# hamilton-3c.net
KiCad netlist of a schematic drawn in EAGLE
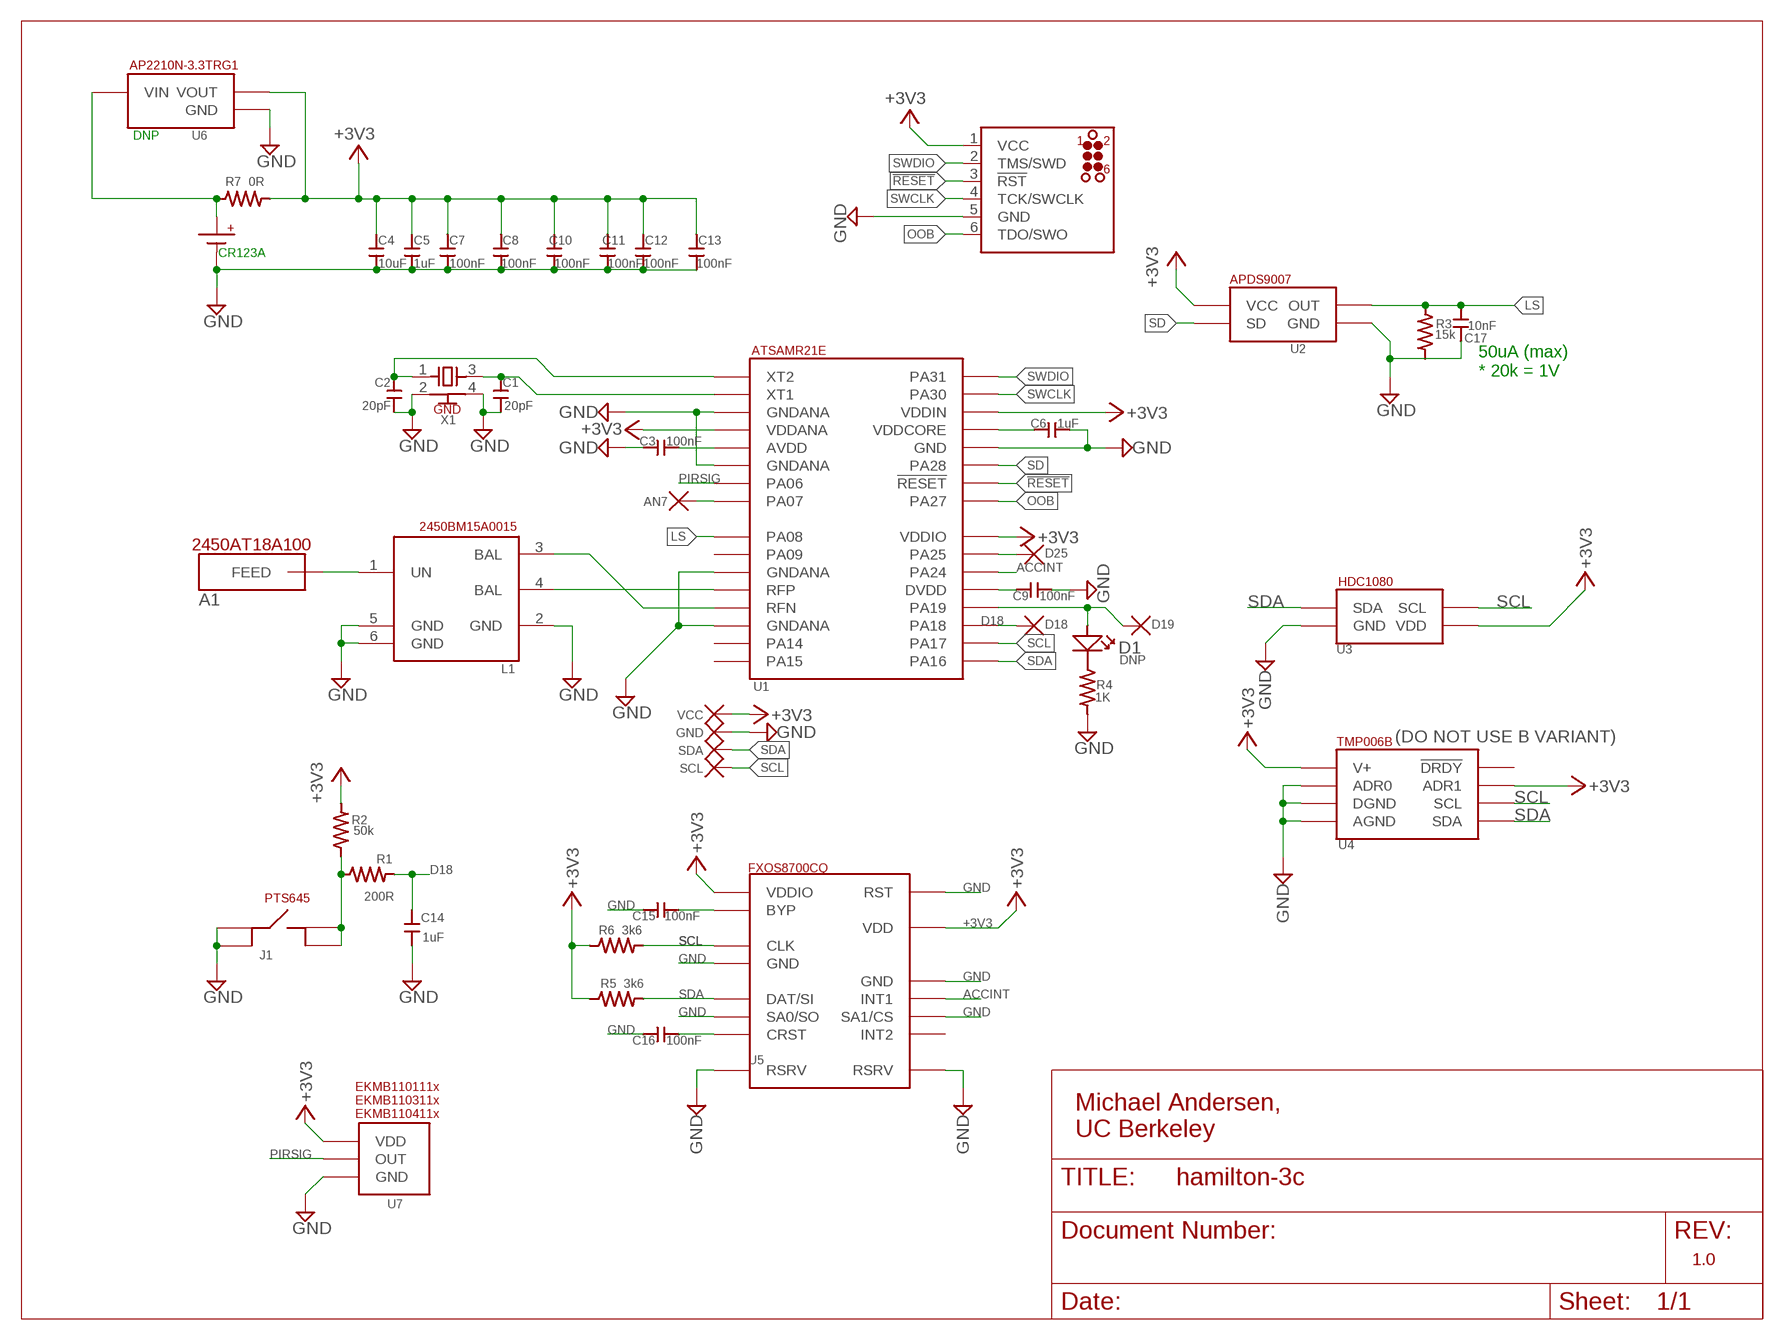
[diagram p0: schematic, sheet 1]

(export (version "E")
  (design (tool "Eeschema 10.0.6"))
  (components
    (comp (ref "A1")
      (value "JOHANSON_ANTENNA2")
      (footprint "eagle-import:JOHANSON_ANTENNA2")
      (libsource (lib "eagle-import") (part "JOHANSON_ANTENNA2"))
    )
    (comp (ref "BT1")
      (value "2/3A")
      (footprint "eagle-import:2_3A")
      (libsource (lib "eagle-import") (part "2/3A"))
    )
    (comp (ref "C1")
      (value "20pF")
      (footprint "eagle-import:S0402")
      (libsource (lib "eagle-import") (part "0603_CAPACITORSMALL"))
    )
    (comp (ref "C2")
      (value "20pF")
      (footprint "eagle-import:S0402")
      (libsource (lib "eagle-import") (part "0603_CAPACITORSMALL"))
    )
    (comp (ref "C3")
      (value "100nF")
      (footprint "eagle-import:S0402")
      (libsource (lib "eagle-import") (part "0603_CAPACITORSMALL"))
    )
    (comp (ref "C4")
      (value "10uF")
      (footprint "eagle-import:0805")
      (libsource (lib "eagle-import") (part "0805_CAPACITOR"))
    )
    (comp (ref "C5")
      (value "1uF")
      (footprint "eagle-import:S0402")
      (libsource (lib "eagle-import") (part "0603_CAPACITORSMALL"))
    )
    (comp (ref "C6")
      (value "1uF")
      (footprint "eagle-import:S0402")
      (libsource (lib "eagle-import") (part "0603_CAPACITORSMALL"))
    )
    (comp (ref "C7")
      (value "100nF")
      (footprint "eagle-import:S0402")
      (libsource (lib "eagle-import") (part "0603_CAPACITORSMALL"))
    )
    (comp (ref "C8")
      (value "100nF")
      (footprint "eagle-import:S0402")
      (libsource (lib "eagle-import") (part "0603_CAPACITORSMALL"))
    )
    (comp (ref "C9")
      (value "100nF")
      (footprint "eagle-import:S0402")
      (libsource (lib "eagle-import") (part "0603_CAPACITORSMALL"))
    )
    (comp (ref "C10")
      (value "100nF")
      (footprint "eagle-import:S0402")
      (libsource (lib "eagle-import") (part "0603_CAPACITORSMALL"))
    )
    (comp (ref "C11")
      (value "100nF")
      (footprint "eagle-import:S0402")
      (libsource (lib "eagle-import") (part "0603_CAPACITORSMALL"))
    )
    (comp (ref "C12")
      (value "100nF")
      (footprint "eagle-import:S0402")
      (libsource (lib "eagle-import") (part "0603_CAPACITORSMALL"))
    )
    (comp (ref "C13")
      (value "100nF")
      (footprint "eagle-import:S0402")
      (libsource (lib "eagle-import") (part "0603_CAPACITORSMALL"))
    )
    (comp (ref "C14")
      (value "1uF")
      (footprint "eagle-import:S0402")
      (libsource (lib "eagle-import") (part "0603_CAPACITORSMALL"))
    )
    (comp (ref "C15")
      (value "100nF")
      (footprint "eagle-import:S0402")
      (libsource (lib "eagle-import") (part "0603_CAPACITORSMALL"))
    )
    (comp (ref "C16")
      (value "100nF")
      (footprint "eagle-import:S0402")
      (libsource (lib "eagle-import") (part "0603_CAPACITORSMALL"))
    )
    (comp (ref "C17")
      (value "10nF")
      (footprint "eagle-import:S0402")
      (libsource (lib "eagle-import") (part "0603_CAPACITORSMALL"))
    )
    (comp (ref "D1")
      (value "DNP")
      (footprint "eagle-import:LINE_0603")
      (libsource (lib "eagle-import") (part "STATLEDLINE"))
    )
    (comp (ref "J1")
      (value "PTS645")
      (footprint "eagle-import:PTS645")
      (libsource (lib "eagle-import") (part "PTS645"))
    )
    (comp (ref "L1")
      (value "BALUN_JOHANSON")
      (footprint "eagle-import:BALUN_JOHANSON")
      (libsource (lib "eagle-import") (part "BALUN_JOHANSON"))
    )
    (comp (ref "R1")
      (value "200R")
      (footprint "eagle-import:S0402")
      (libsource (lib "eagle-import") (part "0603_RESISTORSMALL"))
    )
    (comp (ref "R2")
      (value "50k")
      (footprint "eagle-import:S0402")
      (libsource (lib "eagle-import") (part "0603_RESISTORSMALL"))
    )
    (comp (ref "R3")
      (value "15k")
      (footprint "eagle-import:S0402")
      (libsource (lib "eagle-import") (part "0603_RESISTORSMALL"))
    )
    (comp (ref "R4")
      (value "1K")
      (footprint "eagle-import:S0402")
      (libsource (lib "eagle-import") (part "0603_RESISTORSMALL"))
    )
    (comp (ref "R5")
      (value "3k6")
      (footprint "eagle-import:S0402")
      (libsource (lib "eagle-import") (part "0603_RESISTORSMALL"))
    )
    (comp (ref "R6")
      (value "3k6")
      (footprint "eagle-import:S0402")
      (libsource (lib "eagle-import") (part "0603_RESISTORSMALL"))
    )
    (comp (ref "R7")
      (value "0R")
      (footprint "eagle-import:S0402")
      (libsource (lib "eagle-import") (part "0603_RESISTORSMALL"))
    )
    (comp (ref "TP1")
      (value "D19")
      (footprint "eagle-import:TPP")
      (libsource (lib "eagle-import") (part "TP"))
    )
    (comp (ref "TP2")
      (value "D18")
      (footprint "eagle-import:TPP")
      (libsource (lib "eagle-import") (part "TP"))
    )
    (comp (ref "TP3")
      (value "AN7")
      (footprint "eagle-import:TPP")
      (libsource (lib "eagle-import") (part "TP"))
    )
    (comp (ref "TP4")
      (value "D25")
      (footprint "eagle-import:TPP")
      (libsource (lib "eagle-import") (part "TP"))
    )
    (comp (ref "TP5")
      (value "VCC")
      (footprint "eagle-import:TPP")
      (libsource (lib "eagle-import") (part "TP"))
    )
    (comp (ref "TP6")
      (value "GND")
      (footprint "eagle-import:TPP")
      (libsource (lib "eagle-import") (part "TP"))
    )
    (comp (ref "TP7")
      (value "SDA")
      (footprint "eagle-import:TPP")
      (libsource (lib "eagle-import") (part "TP"))
    )
    (comp (ref "TP8")
      (value "SCL")
      (footprint "eagle-import:TPP")
      (libsource (lib "eagle-import") (part "TP"))
    )
    (comp (ref "U$1")
      (value "JLINK_CONNECTWL")
      (footprint "eagle-import:TC2030-MCP")
      (libsource (lib "eagle-import") (part "JLINK_CONNECTWL"))
    )
    (comp (ref "U1")
      (value "SAMR21")
      (footprint "eagle-import:QFN32")
      (libsource (lib "eagle-import") (part "SAMR21"))
    )
    (comp (ref "U2")
      (value "APDS9007")
      (footprint "eagle-import:APDS9007")
      (libsource (lib "eagle-import") (part "APDS9007"))
    )
    (comp (ref "U3")
      (value "HDC1080")
      (footprint "eagle-import:WSON_HDC1080")
      (libsource (lib "eagle-import") (part "HDC1080"))
    )
    (comp (ref "U4")
      (value "TMP006B")
      (footprint "eagle-import:TMP006")
      (libsource (lib "eagle-import") (part "TMP006B"))
    )
    (comp (ref "U5")
      (value "ACCEL_FXOS8700CQ")
      (footprint "eagle-import:TQFN16")
      (libsource (lib "eagle-import") (part "ACCEL_FXOS8700CQ"))
    )
    (comp (ref "U6")
      (value "SOT23-3VREG")
      (footprint "eagle-import:SOT23")
      (libsource (lib "eagle-import") (part "SOT23-3VREG"))
    )
    (comp (ref "U7")
      (value "PANASONIC_PIR")
      (footprint "eagle-import:PIR")
      (libsource (lib "eagle-import") (part "PANASONIC_PIR"))
    )
    (comp (ref "X1")
      (value "XTAL")
      (footprint "eagle-import:XTAL")
      (libsource (lib "eagle-import") (part "XTAL"))
    )
  )
  (nets
    (net (code "1") (name "+3V3") (class "Default")
      (node (ref "C10") (pin "P$1") (pinfunction "P$1_P$1") (pintype "passive"))
      (node (ref "C11") (pin "P$1") (pinfunction "P$1_P$1") (pintype "passive"))
      (node (ref "C12") (pin "P$1") (pinfunction "P$1_P$1") (pintype "passive"))
      (node (ref "C13") (pin "P$1") (pinfunction "P$1_P$1") (pintype "passive"))
      (node (ref "C4") (pin "2") (pinfunction "P$2_2") (pintype "passive"))
      (node (ref "C5") (pin "P$2") (pinfunction "P$2_P$2") (pintype "passive"))
      (node (ref "C7") (pin "P$1") (pinfunction "P$1_P$1") (pintype "passive"))
      (node (ref "C8") (pin "P$1") (pinfunction "P$1_P$1") (pintype "passive"))
      (node (ref "R2") (pin "P$1") (pinfunction "P$1_P$1") (pintype "passive"))
      (node (ref "R5") (pin "P$2") (pinfunction "P$2_P$2") (pintype "passive"))
      (node (ref "R6") (pin "P$2") (pinfunction "P$2_P$2") (pintype "passive"))
      (node (ref "R7") (pin "P$1") (pinfunction "P$1_P$1") (pintype "passive"))
      (node (ref "TP5") (pin "P$1") (pinfunction "P$1_P$1") (pintype "bidirectional"))
      (node (ref "U$1") (pin "1") (pinfunction "VCC_1") (pintype "passive"))
      (node (ref "U1") (pin "24") (pinfunction "VDDIO_24") (pintype "bidirectional"))
      (node (ref "U1") (pin "30") (pinfunction "VDDIN_30") (pintype "bidirectional"))
      (node (ref "U1") (pin "4") (pinfunction "VDDANA_4") (pintype "bidirectional"))
      (node (ref "U2") (pin "4") (pinfunction "VCC_4") (pintype "bidirectional"))
      (node (ref "U3") (pin "5") (pinfunction "VDD_5") (pintype "bidirectional"))
      (node (ref "U4") (pin "A3") (pinfunction "V+_A3") (pintype "bidirectional"))
      (node (ref "U4") (pin "B1") (pinfunction "ADR1_B1") (pintype "bidirectional"))
      (node (ref "U5") (pin "P1") (pinfunction "VDDIO_P1") (pintype "bidirectional"))
      (node (ref "U5") (pin "P14") (pinfunction "VDD_P14") (pintype "bidirectional"))
      (node (ref "U6") (pin "2") (pinfunction "VOUT_2") (pintype "bidirectional"))
      (node (ref "U7") (pin "VDD") (pinfunction "VDD_VDD") (pintype "bidirectional"))
    )
    (net (code "2") (name "/ACCINT") (class "Default")
      (node (ref "U1") (pin "22") (pinfunction "PA24_22") (pintype "bidirectional"))
      (node (ref "U5") (pin "P11") (pinfunction "INT1_P11") (pintype "bidirectional"))
    )
    (net (code "3") (name "/D18") (class "Default")
      (node (ref "C14") (pin "P$2") (pinfunction "P$2_P$2") (pintype "passive"))
      (node (ref "R1") (pin "P$1") (pinfunction "P$1_P$1") (pintype "passive"))
      (node (ref "TP2") (pin "P$1") (pinfunction "P$1_P$1") (pintype "bidirectional"))
      (node (ref "U1") (pin "19") (pinfunction "PA18_19") (pintype "bidirectional"))
    )
    (net (code "4") (name "/PIRSIG") (class "Default")
      (node (ref "U1") (pin "7") (pinfunction "PA06_7") (pintype "bidirectional"))
      (node (ref "U7") (pin "OUT") (pinfunction "OUT_OUT") (pintype "bidirectional"))
    )
    (net (code "5") (name "/~{RESET}") (class "Default")
      (node (ref "U$1") (pin "3") (pinfunction "~{RST}_3") (pintype "bidirectional"))
      (node (ref "U1") (pin "26") (pinfunction "~{RESET}_26") (pintype "bidirectional"))
    )
    (net (code "6") (name "GND") (class "Default")
      (node (ref "BT1") (pin "NEG") (pinfunction "-_NEG") (pintype "bidirectional"))
      (node (ref "C1") (pin "P$1") (pinfunction "P$1_P$1") (pintype "passive"))
      (node (ref "C10") (pin "P$2") (pinfunction "P$2_P$2") (pintype "passive"))
      (node (ref "C11") (pin "P$2") (pinfunction "P$2_P$2") (pintype "passive"))
      (node (ref "C12") (pin "P$2") (pinfunction "P$2_P$2") (pintype "passive"))
      (node (ref "C13") (pin "P$2") (pinfunction "P$2_P$2") (pintype "passive"))
      (node (ref "C14") (pin "P$1") (pinfunction "P$1_P$1") (pintype "passive"))
      (node (ref "C15") (pin "P$2") (pinfunction "P$2_P$2") (pintype "passive"))
      (node (ref "C16") (pin "P$2") (pinfunction "P$2_P$2") (pintype "passive"))
      (node (ref "C17") (pin "P$2") (pinfunction "P$2_P$2") (pintype "passive"))
      (node (ref "C2") (pin "P$1") (pinfunction "P$1_P$1") (pintype "passive"))
      (node (ref "C3") (pin "P$2") (pinfunction "P$2_P$2") (pintype "passive"))
      (node (ref "C4") (pin "1") (pinfunction "P$1_1") (pintype "passive"))
      (node (ref "C5") (pin "P$1") (pinfunction "P$1_P$1") (pintype "passive"))
      (node (ref "C6") (pin "P$1") (pinfunction "P$1_P$1") (pintype "passive"))
      (node (ref "C7") (pin "P$2") (pinfunction "P$2_P$2") (pintype "passive"))
      (node (ref "C8") (pin "P$2") (pinfunction "P$2_P$2") (pintype "passive"))
      (node (ref "C9") (pin "P$1") (pinfunction "P$1_P$1") (pintype "passive"))
      (node (ref "J1") (pin "3") (pinfunction "3_3") (pintype "bidirectional"))
      (node (ref "J1") (pin "4") (pinfunction "4_4") (pintype "bidirectional"))
      (node (ref "L1") (pin "2") (pinfunction "GND_2") (pintype "bidirectional"))
      (node (ref "L1") (pin "5") (pinfunction "GND_5") (pintype "bidirectional"))
      (node (ref "L1") (pin "6") (pinfunction "GND_6") (pintype "bidirectional"))
      (node (ref "R3") (pin "P$1") (pinfunction "P$1_P$1") (pintype "passive"))
      (node (ref "R4") (pin "P$1") (pinfunction "P$1_P$1") (pintype "passive"))
      (node (ref "TP6") (pin "P$1") (pinfunction "P$1_P$1") (pintype "bidirectional"))
      (node (ref "U$1") (pin "5") (pinfunction "GND_5") (pintype "power_in"))
      (node (ref "U1") (pin "11") (pinfunction "GNDANA_11") (pintype "bidirectional"))
      (node (ref "U1") (pin "14") (pinfunction "GNDANA_14") (pintype "bidirectional"))
      (node (ref "U1") (pin "28") (pinfunction "GND_28") (pintype "bidirectional"))
      (node (ref "U1") (pin "3") (pinfunction "GNDANA_3") (pintype "bidirectional"))
      (node (ref "U1") (pin "6") (pinfunction "GNDANA_6") (pintype "bidirectional"))
      (node (ref "U2") (pin "1") (pinfunction "GND_1") (pintype "bidirectional"))
      (node (ref "U3") (pin "2") (pinfunction "GND_2") (pintype "bidirectional"))
      (node (ref "U4") (pin "A1") (pinfunction "DGND_A1") (pintype "bidirectional"))
      (node (ref "U4") (pin "A2") (pinfunction "AGND_A2") (pintype "bidirectional"))
      (node (ref "U4") (pin "C1") (pinfunction "ADR0_C1") (pintype "bidirectional"))
      (node (ref "U5") (pin "P10") (pinfunction "SA1/CS_P10") (pintype "bidirectional"))
      (node (ref "U5") (pin "P12") (pinfunction "GND_P12") (pintype "bidirectional"))
      (node (ref "U5") (pin "P13") (pinfunction "RSRV_P13") (pintype "bidirectional"))
      (node (ref "U5") (pin "P16") (pinfunction "RST_P16") (pintype "bidirectional"))
      (node (ref "U5") (pin "P3") (pinfunction "RSRV_P3") (pintype "bidirectional"))
      (node (ref "U5") (pin "P5") (pinfunction "GND_P5") (pintype "bidirectional"))
      (node (ref "U5") (pin "P7") (pinfunction "SA0/SO_P7") (pintype "bidirectional"))
      (node (ref "U6") (pin "1") (pinfunction "GND_1") (pintype "bidirectional"))
      (node (ref "U7") (pin "GND") (pinfunction "GND_GND") (pintype "bidirectional"))
      (node (ref "X1") (pin "2") (pinfunction "GND_2") (pintype "power_in"))
      (node (ref "X1") (pin "4") (pinfunction "GND_4") (pintype "power_in"))
    )
    (net (code "7") (name "LS") (class "Default")
      (node (ref "C17") (pin "P$1") (pinfunction "P$1_P$1") (pintype "passive"))
      (node (ref "R3") (pin "P$2") (pinfunction "P$2_P$2") (pintype "passive"))
      (node (ref "U1") (pin "9") (pinfunction "PA08_9") (pintype "bidirectional"))
      (node (ref "U2") (pin "3") (pinfunction "OUT_3") (pintype "bidirectional"))
    )
    (net (code "8") (name "Net-(BT1-+)") (class "Default")
      (node (ref "BT1") (pin "POS") (pinfunction "+_POS") (pintype "bidirectional"))
      (node (ref "R7") (pin "P$2") (pinfunction "P$2_P$2") (pintype "passive"))
      (node (ref "U6") (pin "3") (pinfunction "VIN_3") (pintype "bidirectional"))
    )
    (net (code "9") (name "Net-(D1-+)") (class "Default")
      (node (ref "D1") (pin "P") (pinfunction "+_P") (pintype "passive"))
      (node (ref "TP1") (pin "P$1") (pinfunction "P$1_P$1") (pintype "bidirectional"))
      (node (ref "U1") (pin "20") (pinfunction "PA19_20") (pintype "bidirectional"))
    )
    (net (code "10") (name "Net-(D1--)") (class "Default")
      (node (ref "D1") (pin "N") (pinfunction "-_N") (pintype "passive"))
      (node (ref "R4") (pin "P$2") (pinfunction "P$2_P$2") (pintype "passive"))
    )
    (net (code "11") (name "Net-(J1-Pad1)") (class "Default")
      (node (ref "J1") (pin "1") (pinfunction "1_1") (pintype "bidirectional"))
      (node (ref "J1") (pin "2") (pinfunction "2_2") (pintype "bidirectional"))
      (node (ref "R1") (pin "P$2") (pinfunction "P$2_P$2") (pintype "passive"))
      (node (ref "R2") (pin "P$2") (pinfunction "P$2_P$2") (pintype "passive"))
    )
    (net (code "12") (name "Net-(L1-UN)") (class "Default")
      (node (ref "A1") (pin "FEED") (pinfunction "FEED_FEED") (pintype "bidirectional"))
      (node (ref "L1") (pin "1") (pinfunction "UN_1") (pintype "bidirectional"))
    )
    (net (code "13") (name "Net-(U1-AVDD)") (class "Default")
      (node (ref "C3") (pin "P$1") (pinfunction "P$1_P$1") (pintype "passive"))
      (node (ref "U1") (pin "5") (pinfunction "AVDD_5") (pintype "bidirectional"))
    )
    (net (code "14") (name "Net-(U1-DVDD)") (class "Default")
      (node (ref "C9") (pin "P$2") (pinfunction "P$2_P$2") (pintype "passive"))
      (node (ref "U1") (pin "21") (pinfunction "DVDD_21") (pintype "bidirectional"))
    )
    (net (code "15") (name "Net-(U1-PA07)") (class "Default")
      (node (ref "TP3") (pin "P$1") (pinfunction "P$1_P$1") (pintype "bidirectional"))
      (node (ref "U1") (pin "8") (pinfunction "PA07_8") (pintype "bidirectional"))
    )
    (net (code "16") (name "Net-(U1-PA25)") (class "Default")
      (node (ref "TP4") (pin "P$1") (pinfunction "P$1_P$1") (pintype "bidirectional"))
      (node (ref "U1") (pin "23") (pinfunction "PA25_23") (pintype "bidirectional"))
    )
    (net (code "17") (name "Net-(U1-RFN)") (class "Default")
      (node (ref "L1") (pin "3") (pinfunction "BAL_3") (pintype "bidirectional"))
      (node (ref "U1") (pin "13") (pinfunction "RFN_13") (pintype "bidirectional"))
    )
    (net (code "18") (name "Net-(U1-RFP)") (class "Default")
      (node (ref "L1") (pin "4") (pinfunction "BAL_4") (pintype "bidirectional"))
      (node (ref "U1") (pin "12") (pinfunction "RFP_12") (pintype "bidirectional"))
    )
    (net (code "19") (name "Net-(U1-VDDCORE)") (class "Default")
      (node (ref "C6") (pin "P$2") (pinfunction "P$2_P$2") (pintype "passive"))
      (node (ref "U1") (pin "29") (pinfunction "VDDCORE_29") (pintype "bidirectional"))
    )
    (net (code "20") (name "Net-(U1-XT1)") (class "Default")
      (node (ref "C1") (pin "P$2") (pinfunction "P$2_P$2") (pintype "passive"))
      (node (ref "U1") (pin "2") (pinfunction "XT1_2") (pintype "bidirectional"))
      (node (ref "X1") (pin "3") (pinfunction "X2_3") (pintype "power_in"))
    )
    (net (code "21") (name "Net-(U1-XT2)") (class "Default")
      (node (ref "C2") (pin "P$2") (pinfunction "P$2_P$2") (pintype "passive"))
      (node (ref "U1") (pin "1") (pinfunction "XT2_1") (pintype "bidirectional"))
      (node (ref "X1") (pin "1") (pinfunction "X1_1") (pintype "power_in"))
    )
    (net (code "22") (name "Net-(U5-BYP)") (class "Default")
      (node (ref "C15") (pin "P$1") (pinfunction "P$1_P$1") (pintype "passive"))
      (node (ref "U5") (pin "P2") (pinfunction "BYP_P2") (pintype "bidirectional"))
    )
    (net (code "23") (name "Net-(U5-CRST)") (class "Default")
      (node (ref "C16") (pin "P$1") (pinfunction "P$1_P$1") (pintype "passive"))
      (node (ref "U5") (pin "P8") (pinfunction "CRST_P8") (pintype "bidirectional"))
    )
    (net (code "24") (name "OOB") (class "Default")
      (node (ref "U$1") (pin "6") (pinfunction "TDO/SWO_6") (pintype "bidirectional"))
      (node (ref "U1") (pin "25") (pinfunction "PA27_25") (pintype "bidirectional"))
    )
    (net (code "25") (name "SCL") (class "Default")
      (node (ref "R6") (pin "P$1") (pinfunction "P$1_P$1") (pintype "passive"))
      (node (ref "TP8") (pin "P$1") (pinfunction "P$1_P$1") (pintype "bidirectional"))
      (node (ref "U1") (pin "18") (pinfunction "PA17_18") (pintype "bidirectional"))
      (node (ref "U3") (pin "6") (pinfunction "SCL_6") (pintype "bidirectional"))
      (node (ref "U4") (pin "B3") (pinfunction "SCL_B3") (pintype "bidirectional"))
      (node (ref "U5") (pin "P4") (pinfunction "CLK_P4") (pintype "bidirectional"))
    )
    (net (code "26") (name "SD") (class "Default")
      (node (ref "U1") (pin "27") (pinfunction "PA28_27") (pintype "bidirectional"))
      (node (ref "U2") (pin "6") (pinfunction "SD_6") (pintype "bidirectional"))
    )
    (net (code "27") (name "SDA") (class "Default")
      (node (ref "R5") (pin "P$1") (pinfunction "P$1_P$1") (pintype "passive"))
      (node (ref "TP7") (pin "P$1") (pinfunction "P$1_P$1") (pintype "bidirectional"))
      (node (ref "U1") (pin "17") (pinfunction "PA16_17") (pintype "bidirectional"))
      (node (ref "U3") (pin "1") (pinfunction "SDA_1") (pintype "bidirectional"))
      (node (ref "U4") (pin "C3") (pinfunction "SDA_C3") (pintype "bidirectional"))
      (node (ref "U5") (pin "P6") (pinfunction "DAT/SI_P6") (pintype "bidirectional"))
    )
    (net (code "28") (name "SWCLK") (class "Default")
      (node (ref "U$1") (pin "4") (pinfunction "TCK/SWCLK_4") (pintype "bidirectional"))
      (node (ref "U1") (pin "31") (pinfunction "PA30_31") (pintype "bidirectional"))
    )
    (net (code "29") (name "SWDIO") (class "Default")
      (node (ref "U$1") (pin "2") (pinfunction "TMS/SWD_2") (pintype "bidirectional"))
      (node (ref "U1") (pin "32") (pinfunction "PA31_32") (pintype "bidirectional"))
    )
    (net (code "30") (name "unconnected-(U1-PA09-Pad10)") (class "Default")
      (node (ref "U1") (pin "10") (pinfunction "PA09_10") (pintype "bidirectional"))
    )
    (net (code "31") (name "unconnected-(U1-PA14-Pad15)") (class "Default")
      (node (ref "U1") (pin "15") (pinfunction "PA14_15") (pintype "bidirectional"))
    )
    (net (code "32") (name "unconnected-(U1-PA15-Pad16)") (class "Default")
      (node (ref "U1") (pin "16") (pinfunction "PA15_16") (pintype "bidirectional"))
    )
    (net (code "33") (name "unconnected-(U4-~{DRDY}-PadC2)") (class "Default")
      (node (ref "U4") (pin "C2") (pinfunction "~{DRDY}_C2") (pintype "bidirectional"))
    )
    (net (code "34") (name "unconnected-(U5-INT2-PadP9)") (class "Default")
      (node (ref "U5") (pin "P9") (pinfunction "INT2_P9") (pintype "bidirectional"))
    )
  )
)
